# 7segment.net
KiCad netlist of a schematic drawn in Altium Designer
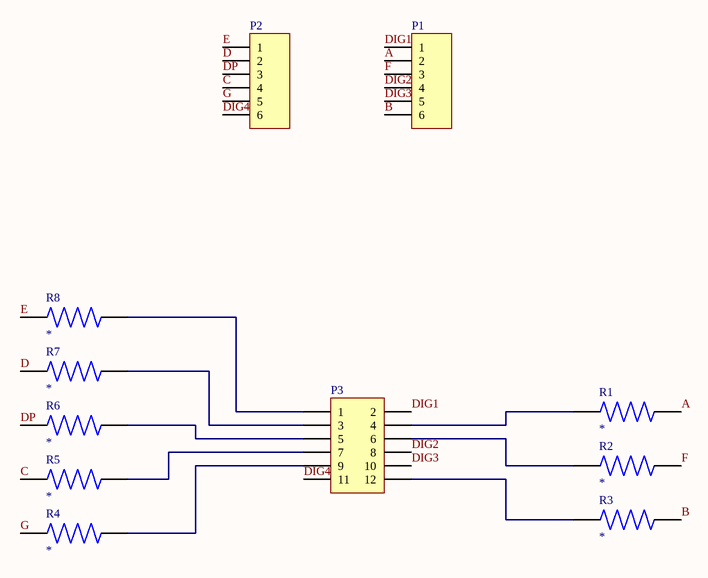
[diagram p0: 7segment.SchDoc]

(export (version "E")
  (design (tool "Eeschema 10.0.6"))
  (components
    (comp (ref "P1")
      (value "Header 6")
      (footprint "HDR1X6")
      (description "Header, 6-Pin")
      (fields (field (name "PUBLISHER") "Altium Limited"))
      (libsource (lib "Miscellaneous Connectors") (part "Header 6"))
    )
    (comp (ref "P2")
      (value "Header 6")
      (footprint "HDR1X6")
      (description "Header, 6-Pin")
      (fields (field (name "PUBLISHER") "Altium Limited"))
      (libsource (lib "Miscellaneous Connectors") (part "Header 6"))
    )
    (comp (ref "P3")
      (value "Header 6X2")
      (footprint "HDR2X6")
      (description "Header, 6-Pin, Dual row")
      (fields (field (name "PUBLISHER") "Altium Limited"))
      (libsource (lib "Miscellaneous Connectors") (part "Header 6X2"))
    )
    (comp (ref "R1")
      (value "1623401-1")
      (footprint "RESC2012X65N")
      (description "Res Thick Film 0805 0 Ohm Molded SMD SMD T/R")
      (fields (field (name "MP") "CRG0805ZR") (field (name "TOLERANCE") "0%") (field (name "COMMENT_1") "*"))
      (libsource (lib "CRG0805ZR") (part "CRG0805ZR"))
    )
    (comp (ref "R2")
      (value "1623401-1")
      (footprint "RESC2012X65N")
      (description "Res Thick Film 0805 0 Ohm Molded SMD SMD T/R")
      (fields (field (name "MP") "CRG0805ZR") (field (name "TOLERANCE") "0%") (field (name "COMMENT_1") "*"))
      (libsource (lib "CRG0805ZR") (part "CRG0805ZR"))
    )
    (comp (ref "R3")
      (value "1623401-1")
      (footprint "RESC2012X65N")
      (description "Res Thick Film 0805 0 Ohm Molded SMD SMD T/R")
      (fields (field (name "MP") "CRG0805ZR") (field (name "TOLERANCE") "0%") (field (name "COMMENT_1") "*"))
      (libsource (lib "CRG0805ZR") (part "CRG0805ZR"))
    )
    (comp (ref "R4")
      (value "1623401-1")
      (footprint "RESC2012X65N")
      (description "Res Thick Film 0805 0 Ohm Molded SMD SMD T/R")
      (fields (field (name "MP") "CRG0805ZR") (field (name "TOLERANCE") "0%") (field (name "COMMENT_1") "*"))
      (libsource (lib "CRG0805ZR") (part "CRG0805ZR"))
    )
    (comp (ref "R5")
      (value "1623401-1")
      (footprint "RESC2012X65N")
      (description "Res Thick Film 0805 0 Ohm Molded SMD SMD T/R")
      (fields (field (name "MP") "CRG0805ZR") (field (name "TOLERANCE") "0%") (field (name "COMMENT_1") "*"))
      (libsource (lib "CRG0805ZR") (part "CRG0805ZR"))
    )
    (comp (ref "R6")
      (value "1623401-1")
      (footprint "RESC2012X65N")
      (description "Res Thick Film 0805 0 Ohm Molded SMD SMD T/R")
      (fields (field (name "MP") "CRG0805ZR") (field (name "TOLERANCE") "0%") (field (name "COMMENT_1") "*"))
      (libsource (lib "CRG0805ZR") (part "CRG0805ZR"))
    )
    (comp (ref "R7")
      (value "1623401-1")
      (footprint "RESC2012X65N")
      (description "Res Thick Film 0805 0 Ohm Molded SMD SMD T/R")
      (fields (field (name "MP") "CRG0805ZR") (field (name "TOLERANCE") "0%") (field (name "COMMENT_1") "*"))
      (libsource (lib "CRG0805ZR") (part "CRG0805ZR"))
    )
    (comp (ref "R8")
      (value "1623401-1")
      (footprint "RESC2012X65N")
      (description "Res Thick Film 0805 0 Ohm Molded SMD SMD T/R")
      (fields (field (name "MP") "CRG0805ZR") (field (name "TOLERANCE") "0%") (field (name "COMMENT_1") "*"))
      (libsource (lib "CRG0805ZR") (part "CRG0805ZR"))
    )
  )
  (nets
    (net (code "1") (name "/A") (class "Default")
      (node (ref "P1") (pin "2") (pinfunction "2_2") (pintype "passive"))
      (node (ref "R1") (pin "2") (pinfunction "2_2") (pintype "passive"))
    )
    (net (code "2") (name "/B") (class "Default")
      (node (ref "P1") (pin "6") (pinfunction "6_6") (pintype "passive"))
      (node (ref "R3") (pin "2") (pinfunction "2_2") (pintype "passive"))
    )
    (net (code "3") (name "/C") (class "Default")
      (node (ref "P2") (pin "4") (pinfunction "4_4") (pintype "passive"))
      (node (ref "R5") (pin "2") (pinfunction "2_2") (pintype "passive"))
    )
    (net (code "4") (name "/D") (class "Default")
      (node (ref "P2") (pin "2") (pinfunction "2_2") (pintype "passive"))
      (node (ref "R7") (pin "2") (pinfunction "2_2") (pintype "passive"))
    )
    (net (code "5") (name "/DIG1") (class "Default")
      (node (ref "P1") (pin "1") (pinfunction "1_1") (pintype "passive"))
      (node (ref "P3") (pin "2") (pinfunction "2_2") (pintype "passive"))
    )
    (net (code "6") (name "/DIG2") (class "Default")
      (node (ref "P1") (pin "4") (pinfunction "4_4") (pintype "passive"))
      (node (ref "P3") (pin "8") (pinfunction "8_8") (pintype "passive"))
    )
    (net (code "7") (name "/DIG3") (class "Default")
      (node (ref "P1") (pin "5") (pinfunction "5_5") (pintype "passive"))
      (node (ref "P3") (pin "10") (pinfunction "10_10") (pintype "passive"))
    )
    (net (code "8") (name "/DIG4") (class "Default")
      (node (ref "P2") (pin "6") (pinfunction "6_6") (pintype "passive"))
      (node (ref "P3") (pin "11") (pinfunction "11_11") (pintype "passive"))
    )
    (net (code "9") (name "/DP") (class "Default")
      (node (ref "P2") (pin "3") (pinfunction "3_3") (pintype "passive"))
      (node (ref "R6") (pin "2") (pinfunction "2_2") (pintype "passive"))
    )
    (net (code "10") (name "/E") (class "Default")
      (node (ref "P2") (pin "1") (pinfunction "1_1") (pintype "passive"))
      (node (ref "R8") (pin "2") (pinfunction "2_2") (pintype "passive"))
    )
    (net (code "11") (name "/F") (class "Default")
      (node (ref "P1") (pin "3") (pinfunction "3_3") (pintype "passive"))
      (node (ref "R2") (pin "2") (pinfunction "2_2") (pintype "passive"))
    )
    (net (code "12") (name "/G") (class "Default")
      (node (ref "P2") (pin "5") (pinfunction "5_5") (pintype "passive"))
      (node (ref "R4") (pin "2") (pinfunction "2_2") (pintype "passive"))
    )
    (net (code "13") (name "Net-(P3-Pad1)") (class "Default")
      (node (ref "P3") (pin "1") (pinfunction "1_1") (pintype "passive"))
      (node (ref "R8") (pin "1") (pinfunction "1_1") (pintype "passive"))
    )
    (net (code "14") (name "Net-(P3-Pad3)") (class "Default")
      (node (ref "P3") (pin "3") (pinfunction "3_3") (pintype "passive"))
      (node (ref "R7") (pin "1") (pinfunction "1_1") (pintype "passive"))
    )
    (net (code "15") (name "Net-(P3-Pad4)") (class "Default")
      (node (ref "P3") (pin "4") (pinfunction "4_4") (pintype "passive"))
      (node (ref "R1") (pin "1") (pinfunction "1_1") (pintype "passive"))
    )
    (net (code "16") (name "Net-(P3-Pad5)") (class "Default")
      (node (ref "P3") (pin "5") (pinfunction "5_5") (pintype "passive"))
      (node (ref "R6") (pin "1") (pinfunction "1_1") (pintype "passive"))
    )
    (net (code "17") (name "Net-(P3-Pad6)") (class "Default")
      (node (ref "P3") (pin "6") (pinfunction "6_6") (pintype "passive"))
      (node (ref "R2") (pin "1") (pinfunction "1_1") (pintype "passive"))
    )
    (net (code "18") (name "Net-(P3-Pad7)") (class "Default")
      (node (ref "P3") (pin "7") (pinfunction "7_7") (pintype "passive"))
      (node (ref "R5") (pin "1") (pinfunction "1_1") (pintype "passive"))
    )
    (net (code "19") (name "Net-(P3-Pad9)") (class "Default")
      (node (ref "P3") (pin "9") (pinfunction "9_9") (pintype "passive"))
      (node (ref "R4") (pin "1") (pinfunction "1_1") (pintype "passive"))
    )
    (net (code "20") (name "Net-(P3-Pad12)") (class "Default")
      (node (ref "P3") (pin "12") (pinfunction "12_12") (pintype "passive"))
      (node (ref "R3") (pin "1") (pinfunction "1_1") (pintype "passive"))
    )
  )
)
